# LNA.net
KiCad netlist of a schematic drawn in Altium Designer
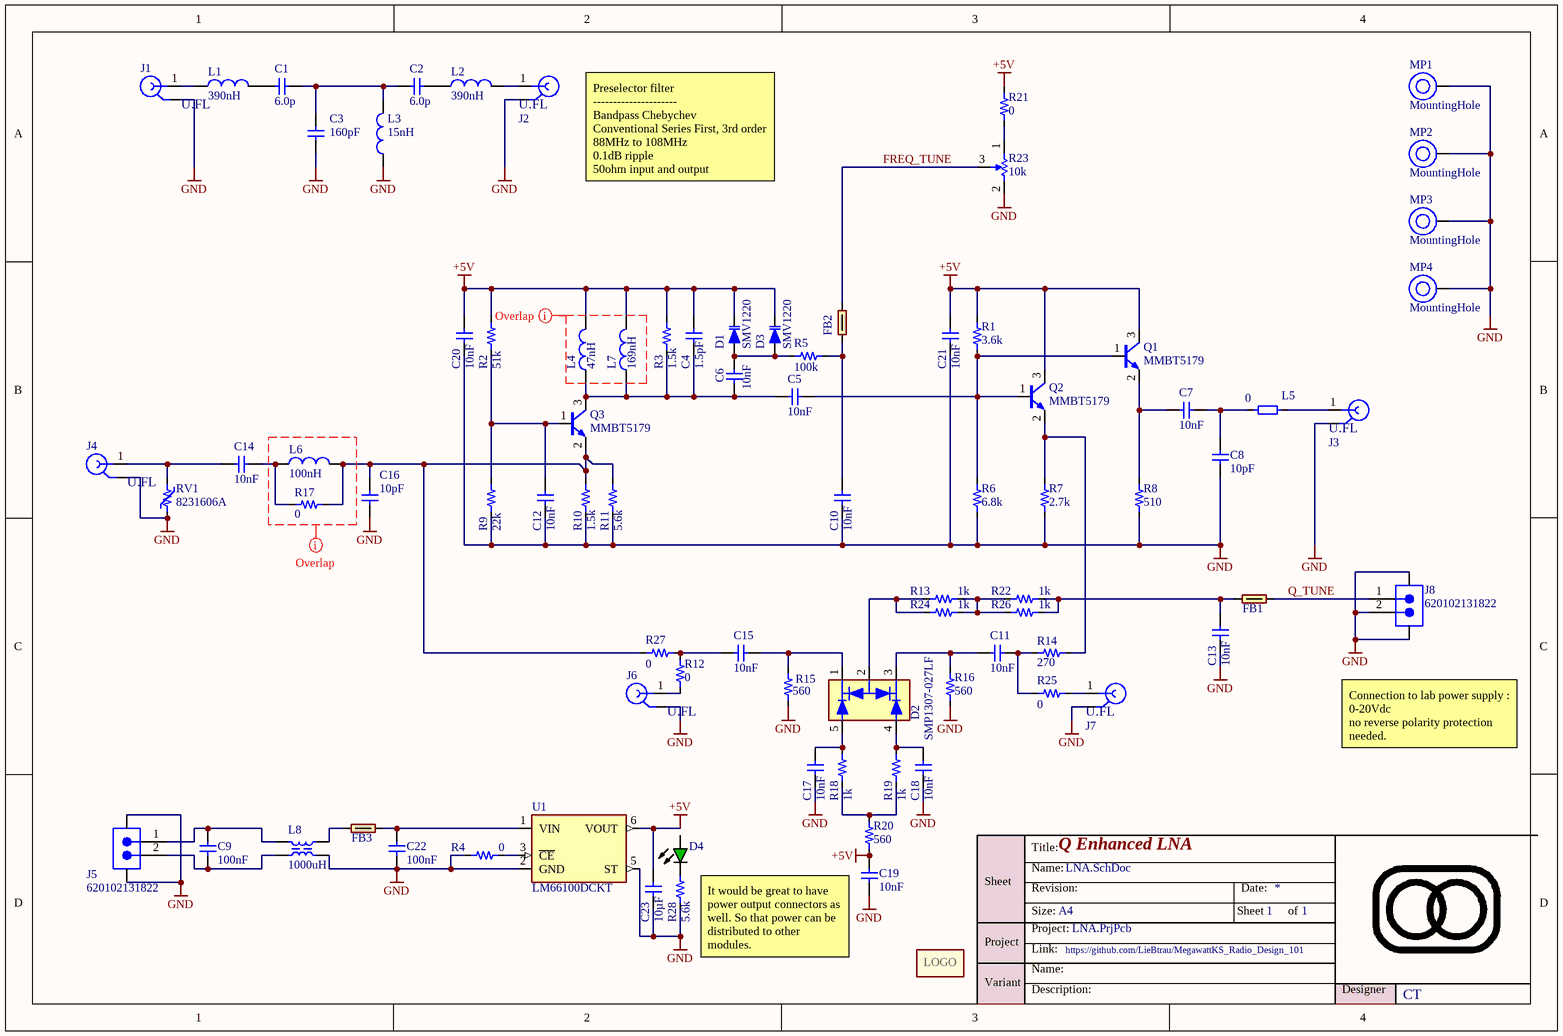
[diagram p0: LNA.SchDoc]

(export (version "E")
  (design (tool "Eeschema 10.0.6"))
  (components
    (comp (ref "C1")
      (value "6.0p")
      (footprint "0603-C-L")
      (description "Multilayer Ceramic Capacitor, 6 pF, 50 V, ± 0.25pF, C0G (NP0), 0603 [1608 Metric]")
      (fields (field (name "Comment") "AC0603CRNPO9BN6R0"))
      (libsource (lib "7c7 Engineering") (part "CAP-NP-2"))
    )
    (comp (ref "C2")
      (value "6.0p")
      (footprint "0603-C-L")
      (description "Multilayer Ceramic Capacitor, 6 pF, 50 V, ± 0.25pF, C0G (NP0), 0603 [1608 Metric]")
      (fields (field (name "Comment") "AC0603CRNPO9BN6R0"))
      (libsource (lib "7c7 Engineering") (part "CAP-NP-2"))
    )
    (comp (ref "C3")
      (value "160pF")
      (footprint "0603-C-N")
      (description "Cap Ceramic 160pF 50V C0G 1% Pad SMD 0603 125C Extreme Low ESR T/R")
      (fields (field (name "TOLERANCE") "1%") (field (name "JLCPCB PART #") "C107041"))
      (libsource (lib "7c7 Engineering") (part "CAP-NP-2"))
    )
    (comp (ref "C4")
      (value "1.5pF")
      (footprint "0603-C-L")
      (description "WCAP-CSGP Multilayer Ceramic Chip Capacitor, General Purpose, size 0603, NP0, 1.5pF, 50VDC")
      (fields
        (field (name "TOLERANCE") "0.5pF")
        (field (name "Comment") "Capacitor 1.5pF +/-0.5pF 50V NP0 0603")
      )
      (libsource (lib "7c7 Engineering") (part "CAP-NP-2"))
    )
    (comp (ref "C5")
      (value "10nF")
      (footprint "0603-C-N")
      (description "Multilayer Ceramic Capacitor, Grm Series, 0.01 F, 5%, C0g / Np0, 50 V, 0603 [1608 Metric]")
      (fields (field (name "VOLTAGE") "50V") (field (name "TOLERANCE") "5%"))
      (libsource (lib "7c7 Engineering") (part "CAP-NP-2"))
    )
    (comp (ref "C6")
      (value "10nF")
      (footprint "0603-C-N")
      (description "Multilayer Ceramic Capacitor, Grm Series, 0.01 F, 5%, C0g / Np0, 50 V, 0603 [1608 Metric]")
      (fields (field (name "VOLTAGE") "50V") (field (name "TOLERANCE") "5%"))
      (libsource (lib "7c7 Engineering") (part "CAP-NP-2"))
    )
    (comp (ref "C7")
      (value "10nF")
      (footprint "0603-C-N")
      (description "Multilayer Ceramic Capacitor, Grm Series, 0.01 F, 5%, C0g / Np0, 50 V, 0603 [1608 Metric]")
      (fields (field (name "VOLTAGE") "50V") (field (name "TOLERANCE") "5%"))
      (libsource (lib "7c7 Engineering") (part "CAP-NP-2"))
    )
    (comp (ref "C8")
      (value "10pF")
      (footprint "0603-C-N")
      (description "WCAP-CSGP Multilayer Ceramic Chip Capacitor, General Purpose, size 0603, NP0, 10pF, 50VDC")
      (fields (field (name "JLCPCB PART #") "C106245") (field (name "TOLERANCE") "5%"))
      (libsource (lib "7c7 Engineering") (part "CAP-NP-2"))
    )
    (comp (ref "C9")
      (value "100nF")
      (footprint "0603-C-N")
      (description "WCAP-CSGP Multilayer Ceramic Chip Capacitor, General Purpose, size 0603, X7R, 100nF, 50VDC")
      (fields (field (name "TOLERANCE") "10%") (field (name "JLCPCB PART #") "C14663"))
      (libsource (lib "7c7 Engineering") (part "CAP-NP-2"))
    )
    (comp (ref "C10")
      (value "10nF")
      (footprint "0603-C-N")
      (description "Multilayer Ceramic Capacitor, Grm Series, 0.01 F, 5%, C0g / Np0, 50 V, 0603 [1608 Metric]")
      (fields (field (name "VOLTAGE") "50V") (field (name "TOLERANCE") "5%"))
      (libsource (lib "7c7 Engineering") (part "CAP-NP-2"))
    )
    (comp (ref "C11")
      (value "10nF")
      (footprint "0603-C-N")
      (description "Multilayer Ceramic Capacitor, Grm Series, 0.01 F, 5%, C0g / Np0, 50 V, 0603 [1608 Metric]")
      (fields (field (name "VOLTAGE") "50V") (field (name "TOLERANCE") "5%"))
      (libsource (lib "7c7 Engineering") (part "CAP-NP-2"))
    )
    (comp (ref "C12")
      (value "10nF")
      (footprint "0603-C-N")
      (description "Multilayer Ceramic Capacitor, Grm Series, 0.01 F, 5%, C0g / Np0, 50 V, 0603 [1608 Metric]")
      (fields (field (name "VOLTAGE") "50V") (field (name "TOLERANCE") "5%"))
      (libsource (lib "7c7 Engineering") (part "CAP-NP-2"))
    )
    (comp (ref "C13")
      (value "10nF")
      (footprint "0603-C-N")
      (description "Multilayer Ceramic Capacitor, Grm Series, 0.01 F, 5%, C0g / Np0, 50 V, 0603 [1608 Metric]")
      (fields (field (name "VOLTAGE") "50V") (field (name "TOLERANCE") "5%"))
      (libsource (lib "7c7 Engineering") (part "CAP-NP-2"))
    )
    (comp (ref "C14")
      (value "10nF")
      (footprint "0603-C-N")
      (description "Multilayer Ceramic Capacitor, Grm Series, 0.01 F, 5%, C0g / Np0, 50 V, 0603 [1608 Metric]")
      (fields (field (name "VOLTAGE") "50V") (field (name "TOLERANCE") "5%"))
      (libsource (lib "7c7 Engineering") (part "CAP-NP-2"))
    )
    (comp (ref "C15")
      (value "10nF")
      (footprint "0603-C-N")
      (description "Multilayer Ceramic Capacitor, Grm Series, 0.01 F, 5%, C0g / Np0, 50 V, 0603 [1608 Metric]")
      (fields (field (name "VOLTAGE") "50V") (field (name "TOLERANCE") "5%"))
      (libsource (lib "7c7 Engineering") (part "CAP-NP-2"))
    )
    (comp (ref "C16")
      (value "10pF")
      (footprint "0603-C-N")
      (description "WCAP-CSGP Multilayer Ceramic Chip Capacitor, General Purpose, size 0603, NP0, 10pF, 50VDC")
      (fields (field (name "TOLERANCE") "5%") (field (name "JLCPCB PART #") "C106245"))
      (libsource (lib "7c7 Engineering") (part "CAP-NP-2"))
    )
    (comp (ref "C17")
      (value "10nF")
      (footprint "0603-C-N")
      (description "Multilayer Ceramic Capacitor, Grm Series, 0.01 F, 5%, C0g / Np0, 50 V, 0603 [1608 Metric]")
      (fields (field (name "VOLTAGE") "50V") (field (name "TOLERANCE") "5%"))
      (libsource (lib "7c7 Engineering") (part "CAP-NP-2"))
    )
    (comp (ref "C18")
      (value "10nF")
      (footprint "0603-C-N")
      (description "Multilayer Ceramic Capacitor, Grm Series, 0.01 F, 5%, C0g / Np0, 50 V, 0603 [1608 Metric]")
      (fields (field (name "VOLTAGE") "50V") (field (name "TOLERANCE") "5%"))
      (libsource (lib "7c7 Engineering") (part "CAP-NP-2"))
    )
    (comp (ref "C19")
      (value "10nF")
      (footprint "0603-C-N")
      (description "Multilayer Ceramic Capacitor, Grm Series, 0.01 F, 5%, C0g / Np0, 50 V, 0603 [1608 Metric]")
      (fields (field (name "VOLTAGE") "50V") (field (name "TOLERANCE") "5%"))
      (libsource (lib "7c7 Engineering") (part "CAP-NP-2"))
    )
    (comp (ref "C20")
      (value "10nF")
      (footprint "0603-C-N")
      (description "Multilayer Ceramic Capacitor, Grm Series, 0.01 F, 5%, C0g / Np0, 50 V, 0603 [1608 Metric]")
      (fields (field (name "VOLTAGE") "50V") (field (name "TOLERANCE") "5%"))
      (libsource (lib "7c7 Engineering") (part "CAP-NP-2"))
    )
    (comp (ref "C21")
      (value "10nF")
      (footprint "0603-C-N")
      (description "Multilayer Ceramic Capacitor, Grm Series, 0.01 F, 5%, C0g / Np0, 50 V, 0603 [1608 Metric]")
      (fields (field (name "VOLTAGE") "50V") (field (name "TOLERANCE") "5%"))
      (libsource (lib "7c7 Engineering") (part "CAP-NP-2"))
    )
    (comp (ref "C22")
      (value "100nF")
      (footprint "0603-C-N")
      (description "WCAP-CSGP Multilayer Ceramic Chip Capacitor, General Purpose, size 0603, X7R, 100nF, 50VDC")
      (fields (field (name "TOLERANCE") "10%") (field (name "JLCPCB PART #") "C14663"))
      (libsource (lib "7c7 Engineering") (part "CAP-NP-2"))
    )
    (comp (ref "C23")
      (value "10µF")
      (footprint "WCAP-CSGP_1210_L3.2W2.5H2.5")
      (description "WCAP-CSGP Multilayer Ceramic Chip Capacitor, General Purpose, size 1210, X7R, 10µF, 50VDC")
      (fields (field (name "JLCPCB PART #") "C77102") (field (name "TOLERANCE") "10%"))
      (libsource (lib "7c7 Engineering") (part "CAP-NP-2"))
    )
    (comp (ref "D1")
      (value "SMV1220")
      (footprint "FP-SOD523-MFG")
      (description "Diode, Varactor, SC79 N-Type")
      (fields (field (name "Comment") "SMV1220-079LF"))
      (libsource (lib "7c7 Engineering") (part "DIODE-VARACTOR"))
    )
    (comp (ref "D2")
      (value "SMP1307-027LF")
      (footprint "SOT25-N")
      (description "Dio Sw 0.85V 200V 10MA SOT5")
      (libsource (lib "7c7 Engineering") (part "SMP1307-027LF-Symbol-1"))
    )
    (comp (ref "D3")
      (value "SMV1220")
      (footprint "FP-SOD523-MFG")
      (description "Diode, Varactor, SC79 N-Type")
      (fields (field (name "Comment") "SMV1220-079LF"))
      (libsource (lib "7c7 Engineering") (part "DIODE-VARACTOR"))
    )
    (comp (ref "D4")
      (value "150060GS84000")
      (footprint "WL-SMCW_0603_150060xx8x000")
      (description "WL-SMCW Mono-color Chip LED Waterclear, size 0603, Green, 3.3V, 40°")
      (fields (field (name "JLCPCB PART #") "C7429914") (field (name "MANUFACTURER") "Wurth Elektronik"))
      (libsource (lib "7c7 Engineering") (part "LED-GREEN-2"))
    )
    (comp (ref "FB1")
      (value "742792662")
      (footprint "0603-FB-N")
      (description "WE-CBF SMT EMI Suppression Ferrite Bead, size 0603, 1000O, 0.83A")
      (fields (field (name "JLCPCB PART #") "C180490") (field (name "MANUFACTURER") "Wurth Elektronik"))
      (libsource (lib "") (part "IND_BEAD_1"))
    )
    (comp (ref "FB2")
      (value "742792662")
      (footprint "0603-FB-N")
      (description "WE-CBF SMT EMI Suppression Ferrite Bead, size 0603, 1000O, 0.83A")
      (fields (field (name "JLCPCB PART #") "C180490") (field (name "MANUFACTURER") "Wurth Elektronik"))
      (libsource (lib "7c7 Engineering") (part "IND_BEAD"))
    )
    (comp (ref "FB3")
      (value "742792662")
      (footprint "0603-FB-N")
      (description "WE-CBF SMT EMI Suppression Ferrite Bead, size 0603, 1000O, 0.83A")
      (fields (field (name "JLCPCB PART #") "C180490") (field (name "MANUFACTURER") "Wurth Elektronik"))
      (libsource (lib "") (part "IND_BEAD_1"))
    )
    (comp (ref "J1")
      (value "U.FL-R-SMT(10)")
      (footprint "HRS-U.FL-R-SMT_V")
      (fields (field (name "JLCPCB PART #") "C88373") (field (name "MANUFACTURER") "Hirose Electric"))
      (libsource (lib "") (part "CN_COAX_1"))
    )
    (comp (ref "J2")
      (value "U.FL-R-SMT(10)")
      (footprint "HRS-U.FL-R-SMT_V")
      (fields (field (name "JLCPCB PART #") "C88373") (field (name "MANUFACTURER") "Hirose Electric"))
      (libsource (lib "7c7 Engineering") (part "CN_COAX"))
    )
    (comp (ref "J3")
      (value "U.FL-R-SMT(10)")
      (footprint "HRS-U.FL-R-SMT_V")
      (fields (field (name "JLCPCB PART #") "C88373") (field (name "MANUFACTURER") "Hirose Electric"))
      (libsource (lib "7c7 Engineering") (part "CN_COAX"))
    )
    (comp (ref "J4")
      (value "U.FL-R-SMT(10)")
      (footprint "HRS-U.FL-R-SMT_V")
      (fields (field (name "JLCPCB PART #") "C88373") (field (name "MANUFACTURER") "Hirose Electric"))
      (libsource (lib "") (part "CN_COAX_1"))
    )
    (comp (ref "J5")
      (value "620102131822")
      (footprint "620102131822")
      (description "WR-WTB SMT Male Horizontal Shrouded Header, pitch 2mm, 2p")
      (fields
        (field (name "JLCPCB PART #") "C295747")
        (field (name "PAGE PART #") "K620102131822")
        (field (name "PUBLISHER") "Wurth Elektronik")
      )
      (libsource (lib "7c7 Engineering") (part "HDR_2P_2MP"))
    )
    (comp (ref "J6")
      (value "U.FL-R-SMT(10)")
      (footprint "HRS-U.FL-R-SMT_V")
      (fields (field (name "JLCPCB PART #") "C88373") (field (name "MANUFACTURER") "Hirose Electric"))
      (libsource (lib "") (part "CN_COAX_1"))
    )
    (comp (ref "J7")
      (value "U.FL-R-SMT(10)")
      (footprint "HRS-U.FL-R-SMT_V")
      (fields (field (name "JLCPCB PART #") "C88373") (field (name "MANUFACTURER") "Hirose Electric"))
      (libsource (lib "7c7 Engineering") (part "CN_COAX"))
    )
    (comp (ref "J8")
      (value "620102131822")
      (footprint "620102131822")
      (description "WR-WTB SMT Male Horizontal Shrouded Header, pitch 2mm, 2p")
      (fields
        (field (name "JLCPCB PART #") "C295747")
        (field (name "PAGE PART #") "K620102131822")
        (field (name "PUBLISHER") "Wurth Elektronik")
      )
      (libsource (lib "7c7 Engineering") (part "HDR_2P_2MP"))
    )
    (comp (ref "L1")
      (value "744762239GA")
      (footprint "WE-KI_1008")
      (description "WE-KI SMT Wire Wound Ceramic Inductor, size 1008, 390nH, 0.47A")
      (fields (field (name "INDUCTANCE") "390nH") (field (name "MANUFACTURER") "Wurth Elektronik"))
      (libsource (lib "7c7 Engineering") (part "IND"))
    )
    (comp (ref "L2")
      (value "744762239GA")
      (footprint "WE-KI_1008")
      (description "WE-KI SMT Wire Wound Ceramic Inductor, size 1008, 390nH, 0.47A")
      (fields (field (name "INDUCTANCE") "390nH") (field (name "MANUFACTURER") "Wurth Elektronik"))
      (libsource (lib "7c7 Engineering") (part "IND"))
    )
    (comp (ref "L3")
      (value "744762115GA")
      (footprint "WE-KI_1008")
      (description "WE-KI SMT Wire Wound Ceramic Inductor, size 1008, 15nH, 1A")
      (fields (field (name "INDUCTANCE") "15nH") (field (name "MANUFACTURER") "Wurth Elektronik"))
      (libsource (lib "7c7 Engineering") (part "IND"))
    )
    (comp (ref "L4")
      (value "744912147")
      (footprint "WE-CAIR_4248")
      (description "WE-CAIR SMT Air Coil, size 4248, 47nH, 3A, 5.6mO")
      (fields (field (name "MANUFACTURER") "Wurth Elektronik") (field (name "INDUCTANCE") "47nH"))
      (libsource (lib "7c7 Engineering") (part "IND"))
    )
    (comp (ref "L5")
      (value "0")
      (footprint "1206-R-N")
      (description "Chip Jumper, Thick Film, Jumper, 1206, 250mW, 2A, 0 Ohm, <50 mOhm")
      (fields (field (name "JLCPCB PART #") "C17888") (field (name "TOLERANCE") "50 mOhm"))
      (libsource (lib "") (part "RES_1"))
    )
    (comp (ref "L6")
      (value "744762210GA")
      (footprint "WE-KI_1008")
      (description "WE-KI SMT Wire Wound Ceramic Inductor, size 1008, 100nH, 1A")
      (fields (field (name "MANUFACTURER") "Wurth Elektronik") (field (name "INDUCTANCE") "100nH"))
      (libsource (lib "7c7 Engineering") (part "IND"))
    )
    (comp (ref "L7")
      (value "AIAC-4125C-R169J-T")
      (footprint "WE-CAIR_5910")
      (fields (field (name "INDUCTANCE") "169nH"))
      (libsource (lib "7c7 Engineering") (part "IND"))
    )
    (comp (ref "L8")
      (value "744222")
      (footprint "WE-SL2_L9.2W6H5")
      (description "WE-SL2 SMT Common Mode Line Filter, 1000uH, 0.8A, 0.207Ohm")
      (fields
        (field (name "INDUCTANCE") "1000uH")
        (field (name "MANUFACTURER") "Wurth Elektronik")
        (field (name "JLCPCB PART #") "C2829007")
      )
      (libsource (lib "7c7 Engineering") (part "CM-choke"))
    )
    (comp (ref "M1")
      (value "Logo")
      (footprint "LOGO_9x6mm")
      (libsource (lib "Integrated_Library_LieBtrau") (part "Logo"))
    )
    (comp (ref "MP1")
      (value "MountingHole")
      (footprint "PTH-M3D6.5_VIA-RING")
      (libsource (lib "7c7 Engineering") (part "MECH_NO_BOM"))
    )
    (comp (ref "MP2")
      (value "MountingHole")
      (footprint "PTH-M3D6.5_VIA-RING")
      (libsource (lib "7c7 Engineering") (part "MECH_NO_BOM"))
    )
    (comp (ref "MP3")
      (value "MountingHole")
      (footprint "PTH-M3D6.5_VIA-RING")
      (libsource (lib "7c7 Engineering") (part "MECH_NO_BOM"))
    )
    (comp (ref "MP4")
      (value "MountingHole")
      (footprint "PTH-M3D6.5_VIA-RING")
      (libsource (lib "7c7 Engineering") (part "MECH_NO_BOM"))
    )
    (comp (ref "Q1")
      (value "MMBT5179")
      (footprint "SOT-23-3-N")
      (description "MMBT5179 Series 12 V CE Breakdown .05 A NPN RF Transistor - SOT-23")
      (fields (field (name "JLCPCB PART #") "C416012"))
      (libsource (lib "7c7 Engineering") (part "BJT-NPN-BEC"))
    )
    (comp (ref "Q2")
      (value "MMBT5179")
      (footprint "SOT-23-3-N")
      (description "MMBT5179 Series 12 V CE Breakdown .05 A NPN RF Transistor - SOT-23")
      (fields (field (name "JLCPCB PART #") "C416012"))
      (libsource (lib "7c7 Engineering") (part "BJT-NPN-BEC"))
    )
    (comp (ref "Q3")
      (value "MMBT5179")
      (footprint "SOT-23-3-N")
      (description "MMBT5179 Series 12 V CE Breakdown .05 A NPN RF Transistor - SOT-23")
      (fields (field (name "JLCPCB PART #") "C416012"))
      (libsource (lib "7c7 Engineering") (part "BJT-NPN-BEC"))
    )
    (comp (ref "R1")
      (value "3.6k")
      (footprint "0603-R-N")
      (description "Res Thick Film 0603 3.6K Ohm 1% 0.1W(1/10W) ±100ppm/°C Pad SMD T/R")
      (fields
        (field (name "JLCPCB PART #") "C22980")
        (field (name "Comment") "Resistor 3.6k +/-0.1W 1% 0603")
      )
      (libsource (lib "7c7 Engineering") (part "RES"))
    )
    (comp (ref "R2")
      (value "51k")
      (footprint "0603-R-N")
      (description "100Mw Thick Film Resistors 100Ppm/ 1% 51K 0603 Chip Resistor Surface Mount Rohs")
      (fields (field (name "TOLERANCE") "1%") (field (name "JLCPCB PART #") "C23196"))
      (libsource (lib "7c7 Engineering") (part "RES"))
    )
    (comp (ref "R3")
      (value "1.5k")
      (footprint "0603-R-N")
      (description "Chip Resistor, Thick Film, General Purpose, 0603, 100mW, 50V, 1.5 kOhm, +/-1%")
      (fields (field (name "TOLERANCE") "1%") (field (name "JLCPCB PART #") "C22843"))
      (libsource (lib "7c7 Engineering") (part "RES"))
    )
    (comp (ref "R4")
      (value "0")
      (footprint "0603-R-N")
      (description "Chip Jumper, Thick Film, Jumper, 0603, 100mW, 1A, 0 Ohm, <50 mOhm")
      (fields (field (name "FLIR PART #") "YRES0E-1") (field (name "TOLERANCE") "50 mOhm"))
      (libsource (lib "7c7 Engineering") (part "RES"))
    )
    (comp (ref "R5")
      (value "100k")
      (footprint "0603-R-N")
      (description "Chip Resistor, Thick Film, General Purpose, 0603, 100mW, 50V, 100 kOhm, +/-1%")
      (fields (field (name "TOLERANCE") "1%") (field (name "JLCPCB PART #") "C25803"))
      (libsource (lib "7c7 Engineering") (part "RES"))
    )
    (comp (ref "R6")
      (value "6.8k")
      (footprint "0603-R-N")
      (description "Res Thick Film 0603 6.8K Ohm 1% 0.1W(1/10W) ±100ppm/C Pad SMD T/R")
      (fields (field (name "TOLERANCE") "1%") (field (name "JLCPCB PART #") "C23212"))
      (libsource (lib "7c7 Engineering") (part "RES"))
    )
    (comp (ref "R7")
      (value "2.7k")
      (footprint "0603-R-N")
      (description "Res Thick Film 0603 2.7K Ohm 1% 0.1W(1/10W) ±100ppm/C Pad SMD Automotive T/R")
      (fields (field (name "TOLERANCE") "1%") (field (name "JLCPCB PART #") "C13167"))
      (libsource (lib "7c7 Engineering") (part "RES"))
    )
    (comp (ref "R8")
      (value "510")
      (footprint "0603-R-N")
      (description "SMD Chip Resistor, 510 Ohm, ± 1%, 100 mW, 0603 [1608 Metric], Thick Film, General Purpose")
      (fields (field (name "JLCPCB PART #") "C23193") (field (name "TOLERANCE") "1%"))
      (libsource (lib "7c7 Engineering") (part "RES"))
    )
    (comp (ref "R9")
      (value "22k")
      (footprint "0603-R-N")
      (description "Chip Resistor, Thick Film, General Purpose, 0603, 100mW, 50V, 22 kOhm, +/-1%")
      (fields (field (name "TOLERANCE") "1%") (field (name "JLCPCB PART #") "C31850"))
      (libsource (lib "7c7 Engineering") (part "RES"))
    )
    (comp (ref "R10")
      (value "1.5k")
      (footprint "0603-R-N")
      (description "Chip Resistor, Thick Film, General Purpose, 0603, 100mW, 50V, 1.5 kOhm, +/-1%")
      (fields (field (name "JLCPCB PART #") "C22843") (field (name "TOLERANCE") "1%"))
      (libsource (lib "7c7 Engineering") (part "RES"))
    )
    (comp (ref "R11")
      (value "5.6k")
      (footprint "0603-R-N")
      (description "Res Thick Film 0603 5.6K Ohm 1% 0.1W(1/10W) ±100ppm/C Pad SMD T/R")
      (fields (field (name "JLCPCB PART #") "C23189") (field (name "TOLERANCE") "1%"))
      (libsource (lib "7c7 Engineering") (part "RES"))
    )
    (comp (ref "R12")
      (value "0")
      (footprint "0603-R-N")
      (description "Chip Jumper, Thick Film, Jumper, 0603, 100mW, 1A, 0 Ohm, <50 mOhm")
      (fields (field (name "FLIR PART #") "YRES0E-1") (field (name "TOLERANCE") "50 mOhm"))
      (libsource (lib "7c7 Engineering") (part "RES"))
    )
    (comp (ref "R13")
      (value "1k")
      (footprint "0603-R-N")
      (description "Chip Resistor, Thick Film, General Purpose, 0603, 100mW, 50V, 1 kOhm, +/-1%")
      (fields (field (name "JLCPCB PART #") "C21190") (field (name "TOLERANCE") "1%"))
      (libsource (lib "7c7 Engineering") (part "RES"))
    )
    (comp (ref "R14")
      (value "270")
      (footprint "0603-R-N")
      (description "Chip Resistor, Thick Film, General Purpose, 0603, 100mW, 50V, 270 Ohm, +/-1%")
      (fields (field (name "TOLERANCE") "1%") (field (name "JLCPCB PART #") "C22966"))
      (libsource (lib "7c7 Engineering") (part "RES"))
    )
    (comp (ref "R15")
      (value "560")
      (footprint "0603-R-N")
      (description "SMD Chip Resistor, 560 Ohm, ï¿½ 1%, 100 mW, 0603 [1608 Metric], Thick Film, General Purpose")
      (fields (field (name "JLCPCB PART #") "C23204") (field (name "TOLERANCE") "1%"))
      (libsource (lib "7c7 Engineering") (part "RES"))
    )
    (comp (ref "R16")
      (value "560")
      (footprint "0603-R-N")
      (description "SMD Chip Resistor, 560 Ohm, ï¿½ 1%, 100 mW, 0603 [1608 Metric], Thick Film, General Purpose")
      (fields (field (name "JLCPCB PART #") "C23204") (field (name "TOLERANCE") "1%"))
      (libsource (lib "7c7 Engineering") (part "RES"))
    )
    (comp (ref "R17")
      (value "0")
      (footprint "0805-R-N")
      (description "Chip Jumper, Thick Film, Jumper, 0805, 125mW, 2A, 0 Ohm, <50 mOhm")
      (fields (field (name "TOLERANCE") "50 mOhm") (field (name "Comment") "Jumper 0R <50 mOhm 2A 0805"))
      (libsource (lib "7c7 Engineering") (part "RES"))
    )
    (comp (ref "R18")
      (value "1k")
      (footprint "0603-R-N")
      (description "Chip Resistor, Thick Film, General Purpose, 0603, 100mW, 50V, 1 kOhm, +/-1%")
      (fields (field (name "JLCPCB PART #") "C21190") (field (name "TOLERANCE") "1%"))
      (libsource (lib "7c7 Engineering") (part "RES"))
    )
    (comp (ref "R19")
      (value "1k")
      (footprint "0603-R-N")
      (description "Chip Resistor, Thick Film, General Purpose, 0603, 100mW, 50V, 1 kOhm, +/-1%")
      (fields (field (name "JLCPCB PART #") "C21190") (field (name "TOLERANCE") "1%"))
      (libsource (lib "7c7 Engineering") (part "RES"))
    )
    (comp (ref "R20")
      (value "560")
      (footprint "0603-R-N")
      (description "SMD Chip Resistor, 560 Ohm, ï¿½ 1%, 100 mW, 0603 [1608 Metric], Thick Film, General Purpose")
      (fields (field (name "JLCPCB PART #") "C23204") (field (name "TOLERANCE") "1%"))
      (libsource (lib "7c7 Engineering") (part "RES"))
    )
    (comp (ref "R21")
      (value "0")
      (footprint "0603-R-N")
      (description "Chip Jumper, Thick Film, Jumper, 0603, 100mW, 1A, 0 Ohm, <50 mOhm")
      (fields (field (name "FLIR PART #") "YRES0E-1") (field (name "TOLERANCE") "50 mOhm"))
      (libsource (lib "7c7 Engineering") (part "RES"))
    )
    (comp (ref "R22")
      (value "1k")
      (footprint "0603-R-N")
      (description "Chip Resistor, Thick Film, General Purpose, 0603, 100mW, 50V, 1 kOhm, +/-1%")
      (fields (field (name "JLCPCB PART #") "C21190") (field (name "TOLERANCE") "1%"))
      (libsource (lib "7c7 Engineering") (part "RES"))
    )
    (comp (ref "R23")
      (value "10k")
      (footprint "BOUR-3296W")
      (fields
        (field (name "JLCPCB PART #") "C34846")
        (field (name "TOLERANCE") "10%")
        (field (name "Comment") "3296W-1-103LF")
      )
      (libsource (lib "7c7 Engineering") (part "RES-ADJ-3"))
    )
    (comp (ref "R24")
      (value "1k")
      (footprint "0603-R-N")
      (description "Chip Resistor, Thick Film, General Purpose, 0603, 100mW, 50V, 1 kOhm, +/-1%")
      (fields (field (name "JLCPCB PART #") "C21190") (field (name "TOLERANCE") "1%"))
      (libsource (lib "7c7 Engineering") (part "RES"))
    )
    (comp (ref "R25")
      (value "0")
      (footprint "0603-R-N")
      (description "Chip Jumper, Thick Film, Jumper, 0603, 100mW, 1A, 0 Ohm, <50 mOhm")
      (fields (field (name "FLIR PART #") "YRES0E-1") (field (name "TOLERANCE") "50 mOhm"))
      (libsource (lib "7c7 Engineering") (part "RES"))
    )
    (comp (ref "R26")
      (value "1k")
      (footprint "0603-R-N")
      (description "Chip Resistor, Thick Film, General Purpose, 0603, 100mW, 50V, 1 kOhm, +/-1%")
      (fields (field (name "JLCPCB PART #") "C21190") (field (name "TOLERANCE") "1%"))
      (libsource (lib "7c7 Engineering") (part "RES"))
    )
    (comp (ref "R27")
      (value "0")
      (footprint "0603-R-N")
      (description "Chip Jumper, Thick Film, Jumper, 0603, 100mW, 1A, 0 Ohm, <50 mOhm")
      (fields (field (name "FLIR PART #") "YRES0E-1") (field (name "TOLERANCE") "50 mOhm"))
      (libsource (lib "7c7 Engineering") (part "RES"))
    )
    (comp (ref "R28")
      (value "5.6k")
      (footprint "0603-R-N")
      (description "Res Thick Film 0603 5.6K Ohm 1% 0.1W(1/10W) ±100ppm/C Pad SMD T/R")
      (fields (field (name "JLCPCB PART #") "C23189") (field (name "TOLERANCE") "1%"))
      (libsource (lib "7c7 Engineering") (part "RES"))
    )
    (comp (ref "RV1")
      (value "8231606A")
      (footprint "0603-VAR-N")
      (description "WE-VE femtoF ESD Suppressor, size 0603, 6VDC, 0.05pF")
      (fields (field (name "MANUFACTURER") "Wurth Elektronik"))
      (libsource (lib "7c7 Engineering") (part "RES_VARISTOR"))
    )
    (comp (ref "U1")
      (value "LM66100DCKT")
      (footprint "SOT-363-N")
      (description "1.5-V to 5.5-V, 1.5-A, 0.5-µA IQ ideal diode with integrated FET 6-SC70 -40 to 105")
      (libsource (lib "7c7 Engineering") (part "IC_LM66100"))
    )
  )
  (nets
    (net (code "1") (name "+5V") (class "Default")
      (node (ref "C19") (pin "1") (pinfunction "1_1") (pintype "passive"))
      (node (ref "C20") (pin "1") (pinfunction "1_1") (pintype "passive"))
      (node (ref "C21") (pin "1") (pinfunction "1_1") (pintype "passive"))
      (node (ref "C23") (pin "2") (pinfunction "2_2") (pintype "passive"))
      (node (ref "C4") (pin "2") (pinfunction "2_2") (pintype "passive"))
      (node (ref "D1") (pin "1") (pinfunction "K_1") (pintype "passive"))
      (node (ref "D3") (pin "1") (pinfunction "K_1") (pintype "passive"))
      (node (ref "L4") (pin "2") (pinfunction "2_2") (pintype "passive"))
      (node (ref "L7") (pin "2") (pinfunction "2_2") (pintype "passive"))
      (node (ref "Q1") (pin "3") (pinfunction "C_3") (pintype "passive"))
      (node (ref "Q2") (pin "3") (pinfunction "C_3") (pintype "passive"))
      (node (ref "R1") (pin "2") (pinfunction "2_2") (pintype "passive"))
      (node (ref "R2") (pin "2") (pinfunction "2_2") (pintype "passive"))
      (node (ref "R20") (pin "1") (pinfunction "1_1") (pintype "passive"))
      (node (ref "R21") (pin "2") (pinfunction "2_2") (pintype "passive"))
      (node (ref "R3") (pin "2") (pinfunction "2_2") (pintype "passive"))
      (node (ref "U1") (pin "6") (pinfunction "VOUT_6") (pintype "output"))
    )
    (net (code "2") (name "/FREQ_TUNE") (class "Default")
      (node (ref "FB2") (pin "2") (pinfunction "2_2") (pintype "passive"))
      (node (ref "R23") (pin "3") (pinfunction "TAP_3") (pintype "passive"))
    )
    (net (code "3") (name "/Q_TUNE") (class "Default")
      (node (ref "FB1") (pin "1") (pinfunction "1_1") (pintype "passive"))
      (node (ref "J8") (pin "1") (pinfunction "1_1") (pintype "passive"))
    )
    (net (code "4") (name "GND") (class "Default")
      (node (ref "C10") (pin "2") (pinfunction "2_2") (pintype "passive"))
      (node (ref "C12") (pin "2") (pinfunction "2_2") (pintype "passive"))
      (node (ref "C13") (pin "1") (pinfunction "1_1") (pintype "passive"))
      (node (ref "C16") (pin "1") (pinfunction "1_1") (pintype "passive"))
      (node (ref "C17") (pin "2") (pinfunction "2_2") (pintype "passive"))
      (node (ref "C18") (pin "1") (pinfunction "1_1") (pintype "passive"))
      (node (ref "C19") (pin "2") (pinfunction "2_2") (pintype "passive"))
      (node (ref "C20") (pin "2") (pinfunction "2_2") (pintype "passive"))
      (node (ref "C21") (pin "2") (pinfunction "2_2") (pintype "passive"))
      (node (ref "C22") (pin "1") (pinfunction "1_1") (pintype "passive"))
      (node (ref "C23") (pin "1") (pinfunction "1_1") (pintype "passive"))
      (node (ref "C3") (pin "1") (pinfunction "1_1") (pintype "passive"))
      (node (ref "C8") (pin "2") (pinfunction "2_2") (pintype "passive"))
      (node (ref "J1") (pin "2") (pinfunction "GND_2") (pintype "passive"))
      (node (ref "J2") (pin "2") (pinfunction "GND_2") (pintype "passive"))
      (node (ref "J3") (pin "2") (pinfunction "GND_2") (pintype "passive"))
      (node (ref "J4") (pin "2") (pinfunction "GND_2") (pintype "passive"))
      (node (ref "J5") (pin "MP1") (pinfunction "MP1_MP1") (pintype "passive"))
      (node (ref "J5") (pin "MP2") (pinfunction "MP2_MP2") (pintype "passive"))
      (node (ref "J6") (pin "2") (pinfunction "GND_2") (pintype "passive"))
      (node (ref "J7") (pin "2") (pinfunction "GND_2") (pintype "passive"))
      (node (ref "J8") (pin "2") (pinfunction "2_2") (pintype "passive"))
      (node (ref "J8") (pin "MP1") (pinfunction "MP1_MP1") (pintype "passive"))
      (node (ref "J8") (pin "MP2") (pinfunction "MP2_MP2") (pintype "passive"))
      (node (ref "L3") (pin "1") (pinfunction "1_1") (pintype "passive"))
      (node (ref "L8") (pin "3") (pinfunction "3_3") (pintype "passive"))
      (node (ref "MP1") (pin "1") (pinfunction "H1_1") (pintype "passive"))
      (node (ref "MP2") (pin "1") (pinfunction "H1_1") (pintype "passive"))
      (node (ref "MP3") (pin "1") (pinfunction "H1_1") (pintype "passive"))
      (node (ref "MP4") (pin "1") (pinfunction "H1_1") (pintype "passive"))
      (node (ref "R10") (pin "1") (pinfunction "1_1") (pintype "passive"))
      (node (ref "R11") (pin "1") (pinfunction "1_1") (pintype "passive"))
      (node (ref "R15") (pin "1") (pinfunction "1_1") (pintype "passive"))
      (node (ref "R16") (pin "1") (pinfunction "1_1") (pintype "passive"))
      (node (ref "R23") (pin "2") (pinfunction "B_2") (pintype "passive"))
      (node (ref "R28") (pin "1") (pinfunction "1_1") (pintype "passive"))
      (node (ref "R4") (pin "2") (pinfunction "2_2") (pintype "passive"))
      (node (ref "R6") (pin "1") (pinfunction "1_1") (pintype "passive"))
      (node (ref "R7") (pin "1") (pinfunction "1_1") (pintype "passive"))
      (node (ref "R8") (pin "1") (pinfunction "1_1") (pintype "passive"))
      (node (ref "R9") (pin "1") (pinfunction "1_1") (pintype "passive"))
      (node (ref "RV1") (pin "1") (pinfunction "1_1") (pintype "passive"))
      (node (ref "U1") (pin "2") (pinfunction "GND_2") (pintype "power_in"))
      (node (ref "U1") (pin "5") (pinfunction "ST_5") (pintype "output"))
    )
    (net (code "5") (name "Net-(C1-Pad1)") (class "Default")
      (node (ref "C1") (pin "1") (pinfunction "1_1") (pintype "passive"))
      (node (ref "C2") (pin "2") (pinfunction "2_2") (pintype "passive"))
      (node (ref "C3") (pin "2") (pinfunction "2_2") (pintype "passive"))
      (node (ref "L3") (pin "2") (pinfunction "2_2") (pintype "passive"))
    )
    (net (code "6") (name "Net-(C1-Pad2)") (class "Default")
      (node (ref "C1") (pin "2") (pinfunction "2_2") (pintype "passive"))
      (node (ref "L1") (pin "2") (pinfunction "2_2") (pintype "passive"))
    )
    (net (code "7") (name "Net-(C2-Pad1)") (class "Default")
      (node (ref "C2") (pin "1") (pinfunction "1_1") (pintype "passive"))
      (node (ref "L2") (pin "1") (pinfunction "1_1") (pintype "passive"))
    )
    (net (code "8") (name "Net-(C7-Pad2)") (class "Default")
      (node (ref "C7") (pin "2") (pinfunction "2_2") (pintype "passive"))
      (node (ref "C8") (pin "1") (pinfunction "1_1") (pintype "passive"))
      (node (ref "L5") (pin "1") (pinfunction "1_1") (pintype "passive"))
    )
    (net (code "9") (name "Net-(C9-Pad1)") (class "Default")
      (node (ref "C9") (pin "1") (pinfunction "1_1") (pintype "passive"))
      (node (ref "J5") (pin "2") (pinfunction "2_2") (pintype "passive"))
      (node (ref "L8") (pin "4") (pinfunction "4_4") (pintype "passive"))
    )
    (net (code "10") (name "Net-(C9-Pad2)") (class "Default")
      (node (ref "C9") (pin "2") (pinfunction "2_2") (pintype "passive"))
      (node (ref "J5") (pin "1") (pinfunction "1_1") (pintype "passive"))
      (node (ref "L8") (pin "1") (pinfunction "1_1") (pintype "passive"))
    )
    (net (code "11") (name "Net-(C10-Pad1)") (class "Default")
      (node (ref "C10") (pin "1") (pinfunction "1_1") (pintype "passive"))
      (node (ref "FB2") (pin "1") (pinfunction "1_1") (pintype "passive"))
      (node (ref "R5") (pin "2") (pinfunction "2_2") (pintype "passive"))
    )
    (net (code "12") (name "Net-(C11-Pad1)") (class "Default")
      (node (ref "C11") (pin "1") (pinfunction "1_1") (pintype "passive"))
      (node (ref "R14") (pin "1") (pinfunction "1_1") (pintype "passive"))
      (node (ref "R25") (pin "2") (pinfunction "2_2") (pintype "passive"))
    )
    (net (code "13") (name "Net-(C11-Pad2)") (class "Default")
      (node (ref "C11") (pin "2") (pinfunction "2_2") (pintype "passive"))
      (node (ref "D2") (pin "3") (pinfunction "3_3") (pintype "passive"))
      (node (ref "R16") (pin "2") (pinfunction "2_2") (pintype "passive"))
    )
    (net (code "14") (name "Net-(C13-Pad2)") (class "Default")
      (node (ref "C13") (pin "2") (pinfunction "2_2") (pintype "passive"))
      (node (ref "FB1") (pin "2") (pinfunction "2_2") (pintype "passive"))
      (node (ref "R22") (pin "2") (pinfunction "2_2") (pintype "passive"))
      (node (ref "R26") (pin "2") (pinfunction "2_2") (pintype "passive"))
    )
    (net (code "15") (name "Net-(C14-Pad2)") (class "Default")
      (node (ref "C14") (pin "2") (pinfunction "2_2") (pintype "passive"))
      (node (ref "L6") (pin "1") (pinfunction "1_1") (pintype "passive"))
      (node (ref "R17") (pin "1") (pinfunction "1_1") (pintype "passive"))
    )
    (net (code "16") (name "Net-(C15-Pad1)") (class "Default")
      (node (ref "C15") (pin "1") (pinfunction "1_1") (pintype "passive"))
      (node (ref "D2") (pin "1") (pinfunction "1_1") (pintype "passive"))
      (node (ref "R15") (pin "2") (pinfunction "2_2") (pintype "passive"))
    )
    (net (code "17") (name "Net-(C15-Pad2)") (class "Default")
      (node (ref "C15") (pin "2") (pinfunction "2_2") (pintype "passive"))
      (node (ref "R12") (pin "2") (pinfunction "2_2") (pintype "passive"))
      (node (ref "R27") (pin "1") (pinfunction "1_1") (pintype "passive"))
    )
    (net (code "18") (name "Net-(C17-Pad1)") (class "Default")
      (node (ref "C17") (pin "1") (pinfunction "1_1") (pintype "passive"))
      (node (ref "D2") (pin "5") (pinfunction "5_5") (pintype "passive"))
      (node (ref "R18") (pin "1") (pinfunction "1_1") (pintype "passive"))
    )
    (net (code "19") (name "Net-(C18-Pad2)") (class "Default")
      (node (ref "C18") (pin "2") (pinfunction "2_2") (pintype "passive"))
      (node (ref "D2") (pin "4") (pinfunction "4_4") (pintype "passive"))
      (node (ref "R19") (pin "1") (pinfunction "1_1") (pintype "passive"))
    )
    (net (code "20") (name "Net-(D1-A)") (class "Default")
      (node (ref "C6") (pin "1") (pinfunction "1_1") (pintype "passive"))
      (node (ref "D1") (pin "2") (pinfunction "A_2") (pintype "passive"))
      (node (ref "D3") (pin "2") (pinfunction "A_2") (pintype "passive"))
      (node (ref "R5") (pin "1") (pinfunction "1_1") (pintype "passive"))
    )
    (net (code "21") (name "Net-(D2-Pad2)") (class "Default")
      (node (ref "D2") (pin "2") (pinfunction "2_2") (pintype "passive"))
      (node (ref "R13") (pin "1") (pinfunction "1_1") (pintype "passive"))
      (node (ref "R24") (pin "1") (pinfunction "1_1") (pintype "passive"))
    )
    (net (code "22") (name "Net-(FB3-Pad2)") (class "Default")
      (node (ref "FB3") (pin "2") (pinfunction "2_2") (pintype "passive"))
      (node (ref "L8") (pin "2") (pinfunction "2_2") (pintype "passive"))
    )
    (net (code "23") (name "Net-(J1-SIG)") (class "Default")
      (node (ref "J1") (pin "1") (pinfunction "SIG_1") (pintype "passive"))
      (node (ref "L1") (pin "1") (pinfunction "1_1") (pintype "passive"))
    )
    (net (code "24") (name "Net-(J2-SIG)") (class "Default")
      (node (ref "J2") (pin "1") (pinfunction "SIG_1") (pintype "passive"))
      (node (ref "L2") (pin "2") (pinfunction "2_2") (pintype "passive"))
    )
    (net (code "25") (name "Net-(J3-SIG)") (class "Default")
      (node (ref "J3") (pin "1") (pinfunction "SIG_1") (pintype "passive"))
      (node (ref "L5") (pin "2") (pinfunction "2_2") (pintype "passive"))
    )
    (net (code "26") (name "Net-(J4-SIG)") (class "Default")
      (node (ref "C14") (pin "1") (pinfunction "1_1") (pintype "passive"))
      (node (ref "J4") (pin "1") (pinfunction "SIG_1") (pintype "passive"))
      (node (ref "RV1") (pin "2") (pinfunction "2_2") (pintype "passive"))
    )
    (net (code "27") (name "Net-(J6-SIG)") (class "Default")
      (node (ref "J6") (pin "1") (pinfunction "SIG_1") (pintype "passive"))
      (node (ref "R12") (pin "1") (pinfunction "1_1") (pintype "passive"))
    )
    (net (code "28") (name "Net-(J7-SIG)") (class "Default")
      (node (ref "J7") (pin "1") (pinfunction "SIG_1") (pintype "passive"))
      (node (ref "R25") (pin "1") (pinfunction "1_1") (pintype "passive"))
    )
    (net (code "29") (name "Net-(Q1-B)") (class "Default")
      (node (ref "C5") (pin "2") (pinfunction "2_2") (pintype "passive"))
      (node (ref "Q1") (pin "1") (pinfunction "B_1") (pintype "passive"))
      (node (ref "Q2") (pin "1") (pinfunction "B_1") (pintype "passive"))
      (node (ref "R1") (pin "1") (pinfunction "1_1") (pintype "passive"))
      (node (ref "R6") (pin "2") (pinfunction "2_2") (pintype "passive"))
    )
    (net (code "30") (name "Net-(Q1-E)") (class "Default")
      (node (ref "C7") (pin "1") (pinfunction "1_1") (pintype "passive"))
      (node (ref "Q1") (pin "2") (pinfunction "E_2") (pintype "passive"))
      (node (ref "R8") (pin "2") (pinfunction "2_2") (pintype "passive"))
    )
    (net (code "31") (name "Net-(Q2-E)") (class "Default")
      (node (ref "Q2") (pin "2") (pinfunction "E_2") (pintype "passive"))
      (node (ref "R14") (pin "2") (pinfunction "2_2") (pintype "passive"))
      (node (ref "R7") (pin "2") (pinfunction "2_2") (pintype "passive"))
    )
    (net (code "32") (name "Net-(Q3-B)") (class "Default")
      (node (ref "C12") (pin "1") (pinfunction "1_1") (pintype "passive"))
      (node (ref "Q3") (pin "1") (pinfunction "B_1") (pintype "passive"))
      (node (ref "R2") (pin "1") (pinfunction "1_1") (pintype "passive"))
      (node (ref "R9") (pin "2") (pinfunction "2_2") (pintype "passive"))
    )
    (net (code "33") (name "Net-(Q3-C)") (class "Default")
      (node (ref "C4") (pin "1") (pinfunction "1_1") (pintype "passive"))
      (node (ref "C5") (pin "1") (pinfunction "1_1") (pintype "passive"))
      (node (ref "C6") (pin "2") (pinfunction "2_2") (pintype "passive"))
      (node (ref "L4") (pin "1") (pinfunction "1_1") (pintype "passive"))
      (node (ref "L7") (pin "1") (pinfunction "1_1") (pintype "passive"))
      (node (ref "Q3") (pin "3") (pinfunction "C_3") (pintype "passive"))
      (node (ref "R3") (pin "1") (pinfunction "1_1") (pintype "passive"))
    )
    (net (code "34") (name "Net-(Q3-E)") (class "Default")
      (node (ref "C16") (pin "2") (pinfunction "2_2") (pintype "passive"))
      (node (ref "L6") (pin "2") (pinfunction "2_2") (pintype "passive"))
      (node (ref "Q3") (pin "2") (pinfunction "E_2") (pintype "passive"))
      (node (ref "R10") (pin "2") (pinfunction "2_2") (pintype "passive"))
      (node (ref "R11") (pin "2") (pinfunction "2_2") (pintype "passive"))
      (node (ref "R17") (pin "2") (pinfunction "2_2") (pintype "passive"))
      (node (ref "R27") (pin "2") (pinfunction "2_2") (pintype "passive"))
    )
    (net (code "35") (name "Net-(R13-Pad2)") (class "Default")
      (node (ref "R13") (pin "2") (pinfunction "2_2") (pintype "passive"))
      (node (ref "R22") (pin "1") (pinfunction "1_1") (pintype "passive"))
      (node (ref "R24") (pin "2") (pinfunction "2_2") (pintype "passive"))
      (node (ref "R26") (pin "1") (pinfunction "1_1") (pintype "passive"))
    )
    (net (code "36") (name "Net-(R18-Pad2)") (class "Default")
      (node (ref "R18") (pin "2") (pinfunction "2_2") (pintype "passive"))
      (node (ref "R19") (pin "2") (pinfunction "2_2") (pintype "passive"))
      (node (ref "R20") (pin "2") (pinfunction "2_2") (pintype "passive"))
    )
    (net (code "37") (name "Net-(R23-A)") (class "Default")
      (node (ref "R21") (pin "1") (pinfunction "1_1") (pintype "passive"))
      (node (ref "R23") (pin "1") (pinfunction "A_1") (pintype "passive"))
    )
    (net (code "38") (name "Net-(U1-VIN)") (class "Default")
      (node (ref "C22") (pin "2") (pinfunction "2_2") (pintype "passive"))
      (node (ref "FB3") (pin "1") (pinfunction "1_1") (pintype "passive"))
      (node (ref "U1") (pin "1") (pinfunction "VIN_1") (pintype "power_in"))
    )
    (net (code "39") (name "Net-(U1-~{CE})") (class "Default")
      (node (ref "R4") (pin "1") (pinfunction "1_1") (pintype "passive"))
      (node (ref "U1") (pin "3") (pinfunction "~{CE}_3") (pintype "input"))
    )
    (net (code "40") (name "unconnected-(D4-A-Pad2)") (class "Default")
      (node (ref "D4") (pin "2") (pinfunction "A_2") (pintype "passive"))
    )
    (net (code "41") (name "unconnected-(D4-K-Pad1)") (class "Default")
      (node (ref "D4") (pin "1") (pinfunction "K_1") (pintype "passive"))
    )
    (net (code "42") (name "unconnected-(R28-Pad2)") (class "Default")
      (node (ref "R28") (pin "2") (pinfunction "2_2") (pintype "passive"))
    )
  )
)
